# senseBox-CAM-M8Q_v21.net
KiCad netlist of a schematic drawn in EAGLE
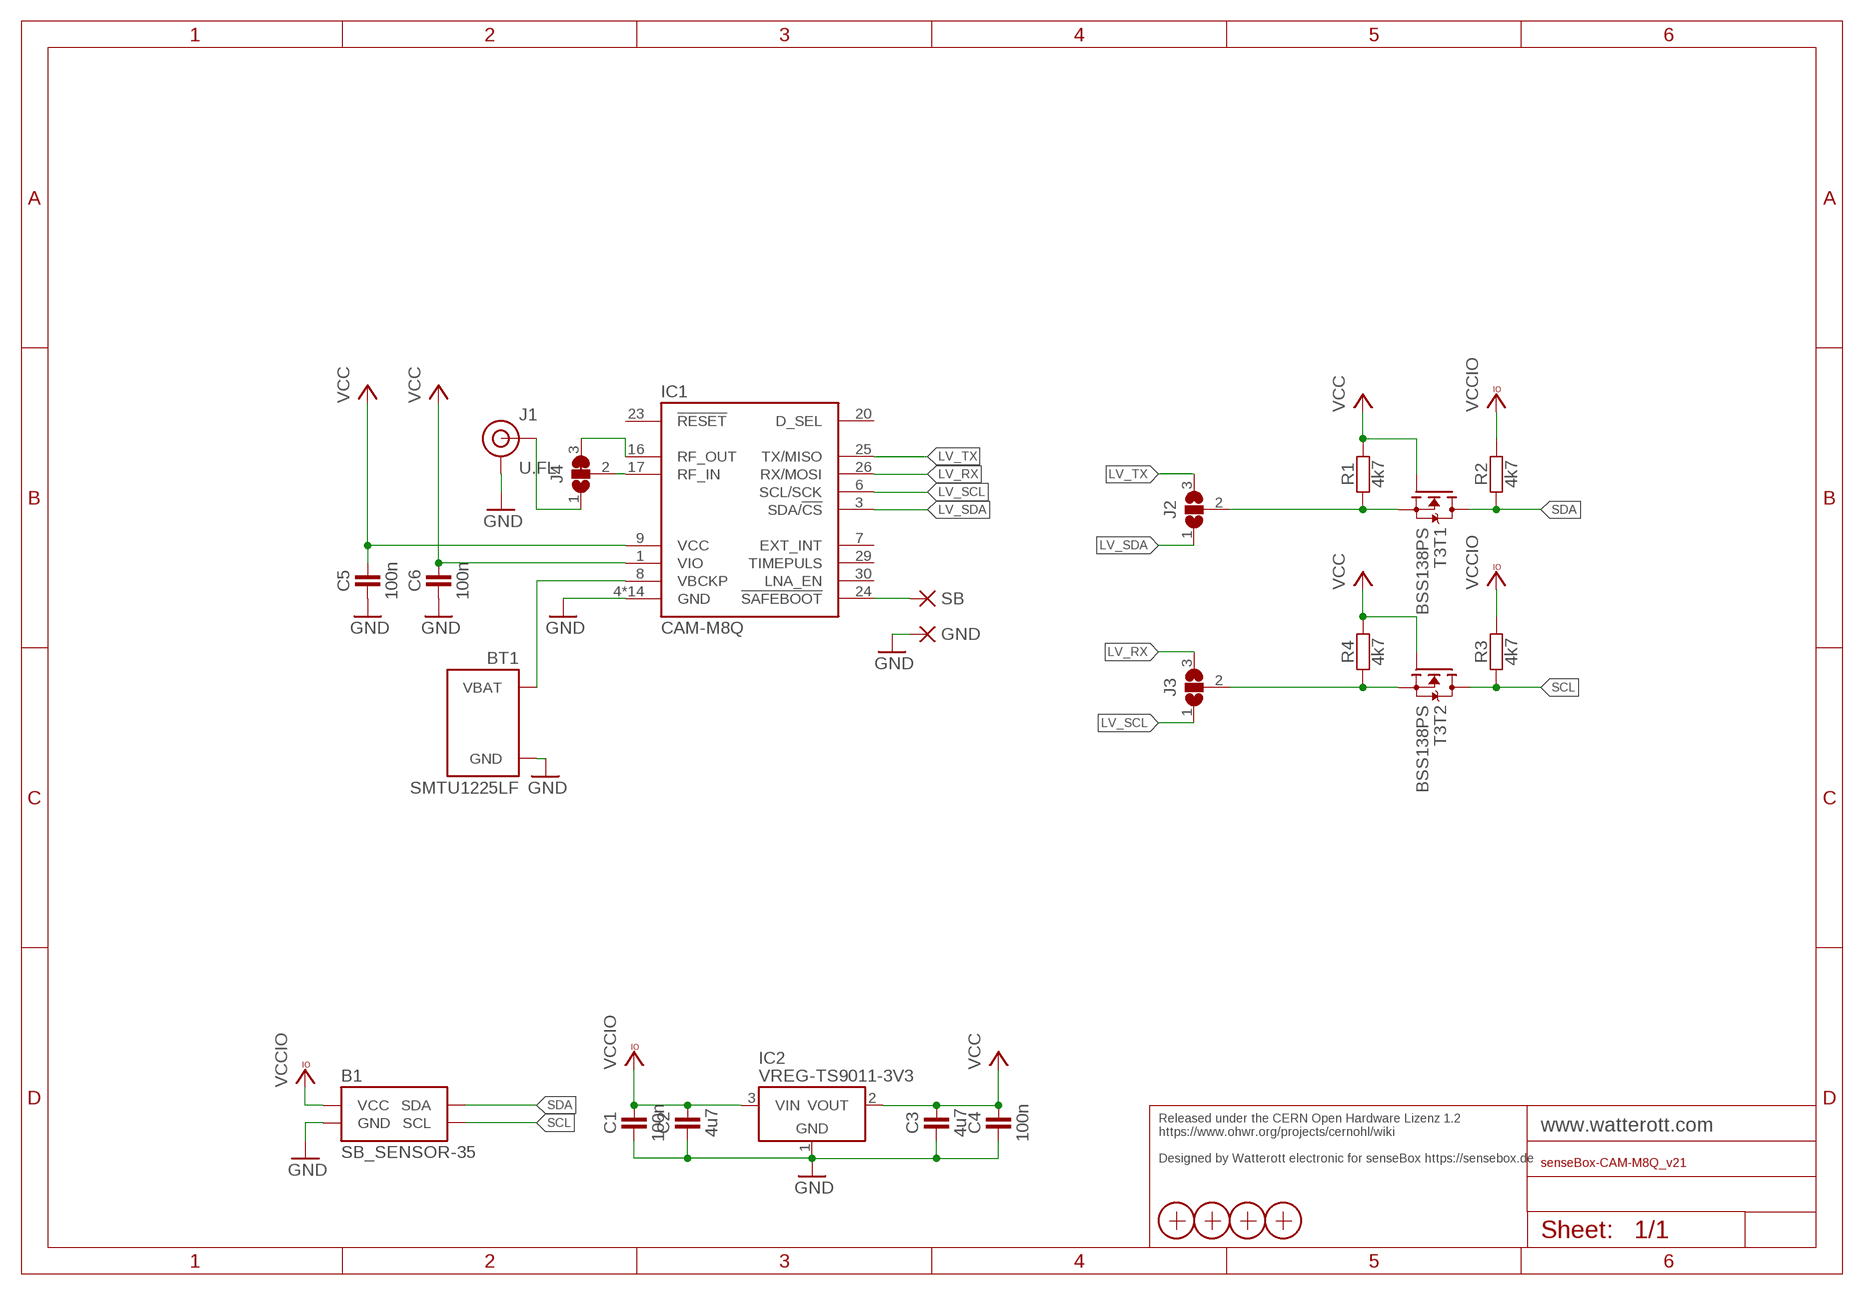
[diagram p0: schematic, sheet 1]

(export (version "E")
  (design (tool "Eeschema 10.0.6"))
  (components
    (comp (ref "B1")
      (value "SB_SENSOR-35")
      (footprint "eagle-import:SB-35X25")
      (libsource (lib "eagle-import") (part "SB_SENSOR-35"))
    )
    (comp (ref "BT1")
      (value "SMTU1225LF")
      (footprint "eagle-import:BAT-SMTU1225LF")
      (libsource (lib "eagle-import") (part "BATTERY-SMTU1225LF"))
    )
    (comp (ref "C1")
      (value "100n")
      (footprint "eagle-import:C0402")
      (libsource (lib "eagle-import") (part "CAPACITOR-0402"))
    )
    (comp (ref "C2")
      (value "4u7")
      (footprint "eagle-import:C0402")
      (libsource (lib "eagle-import") (part "CAPACITOR-0402"))
    )
    (comp (ref "C3")
      (value "4u7")
      (footprint "eagle-import:C0402")
      (libsource (lib "eagle-import") (part "CAPACITOR-0402"))
    )
    (comp (ref "C4")
      (value "100n")
      (footprint "eagle-import:C0402")
      (libsource (lib "eagle-import") (part "CAPACITOR-0402"))
    )
    (comp (ref "C5")
      (value "100n")
      (footprint "eagle-import:C0402")
      (libsource (lib "eagle-import") (part "CAPACITOR-0402"))
    )
    (comp (ref "C6")
      (value "100n")
      (footprint "eagle-import:C0402")
      (libsource (lib "eagle-import") (part "CAPACITOR-0402"))
    )
    (comp (ref "GND")
      (value "PAD-1.27X1.27_NC")
      (footprint "eagle-import:PAD-1.27X1.27_NC")
      (libsource (lib "eagle-import") (part "PAD-1.27X1.27_NC"))
    )
    (comp (ref "IC1")
      (value "CAM-M8Q")
      (footprint "eagle-import:CAM-M8Q")
      (libsource (lib "eagle-import") (part "CAM-M8Q"))
    )
    (comp (ref "IC2")
      (value "VREG-TS9011-3V3")
      (footprint "eagle-import:SOT23")
      (libsource (lib "eagle-import") (part "VREG-TS9011-3V3"))
    )
    (comp (ref "J1")
      (value "U.FL")
      (footprint "eagle-import:U.FL")
      (libsource (lib "eagle-import") (part "U.FL"))
    )
    (comp (ref "J2")
      (value "JUMPER3-0603-NC")
      (footprint "eagle-import:JUMPER3-0603_NC")
      (libsource (lib "eagle-import") (part "JUMPER3-0603-NC"))
    )
    (comp (ref "J3")
      (value "JUMPER3-0603-NC")
      (footprint "eagle-import:JUMPER3-0603_NC")
      (libsource (lib "eagle-import") (part "JUMPER3-0603-NC"))
    )
    (comp (ref "J4")
      (value "JUMPER3-0603")
      (footprint "eagle-import:JUMPER3-0603")
      (libsource (lib "eagle-import") (part "JUMPER3-0603"))
    )
    (comp (ref "R1")
      (value "4k7")
      (footprint "eagle-import:C0402")
      (libsource (lib "eagle-import") (part "RESISTOR-0402"))
    )
    (comp (ref "R2")
      (value "4k7")
      (footprint "eagle-import:C0402")
      (libsource (lib "eagle-import") (part "RESISTOR-0402"))
    )
    (comp (ref "R3")
      (value "4k7")
      (footprint "eagle-import:C0402")
      (libsource (lib "eagle-import") (part "RESISTOR-0402"))
    )
    (comp (ref "R4")
      (value "4k7")
      (footprint "eagle-import:C0402")
      (libsource (lib "eagle-import") (part "RESISTOR-0402"))
    )
    (comp (ref "SB")
      (value "PAD-1.27X1.27_NC")
      (footprint "eagle-import:PAD-1.27X1.27_NC")
      (libsource (lib "eagle-import") (part "PAD-1.27X1.27_NC"))
    )
    (comp (ref "T3")
      (value "BSS138PS")
      (footprint "eagle-import:SOT363")
      (libsource (lib "eagle-import") (part "BSS138PS"))
    )
    (comp (ref "X1")
      (value "PASSER-07")
      (footprint "eagle-import:PASSER_07MM")
      (libsource (lib "eagle-import") (part "PASSER-07"))
    )
    (comp (ref "X2")
      (value "PASSER-07")
      (footprint "eagle-import:PASSER_07MM")
      (libsource (lib "eagle-import") (part "PASSER-07"))
    )
    (comp (ref "X3")
      (value "PASSER-07")
      (footprint "eagle-import:PASSER_07MM")
      (libsource (lib "eagle-import") (part "PASSER-07"))
    )
    (comp (ref "X4")
      (value "PASSER-07")
      (footprint "eagle-import:PASSER_07MM")
      (libsource (lib "eagle-import") (part "PASSER-07"))
    )
  )
  (nets
    (net (code "1") (name "GND") (class "Default")
      (node (ref "B1") (pin "GND") (pinfunction "GND_GND") (pintype "power_in"))
      (node (ref "BT1") (pin "-") (pinfunction "GND_-") (pintype "power_in"))
      (node (ref "C1") (pin "1") (pinfunction "1_1") (pintype "passive"))
      (node (ref "C2") (pin "1") (pinfunction "1_1") (pintype "passive"))
      (node (ref "C3") (pin "1") (pinfunction "1_1") (pintype "passive"))
      (node (ref "C4") (pin "1") (pinfunction "1_1") (pintype "passive"))
      (node (ref "C5") (pin "1") (pinfunction "1_1") (pintype "passive"))
      (node (ref "C6") (pin "1") (pinfunction "1_1") (pintype "passive"))
      (node (ref "GND") (pin "1") (pinfunction "P_1") (pintype "passive"))
      (node (ref "IC1") (pin "10") (pinfunction "GND_10") (pintype "power_in"))
      (node (ref "IC1") (pin "11") (pinfunction "GND_11") (pintype "power_in"))
      (node (ref "IC1") (pin "12") (pinfunction "GND_12") (pintype "power_in"))
      (node (ref "IC1") (pin "13") (pinfunction "GND_13") (pintype "power_in"))
      (node (ref "IC1") (pin "14") (pinfunction "GND_14") (pintype "power_in"))
      (node (ref "IC1") (pin "15") (pinfunction "GND_15") (pintype "power_in"))
      (node (ref "IC1") (pin "18") (pinfunction "GND_18") (pintype "power_in"))
      (node (ref "IC1") (pin "19") (pinfunction "GND_19") (pintype "power_in"))
      (node (ref "IC1") (pin "21") (pinfunction "GND_21") (pintype "power_in"))
      (node (ref "IC1") (pin "22") (pinfunction "GND_22") (pintype "power_in"))
      (node (ref "IC1") (pin "27") (pinfunction "GND_27") (pintype "power_in"))
      (node (ref "IC1") (pin "31") (pinfunction "GND_31") (pintype "power_in"))
      (node (ref "IC1") (pin "4") (pinfunction "GND_4") (pintype "power_in"))
      (node (ref "IC1") (pin "5") (pinfunction "GND_5") (pintype "power_in"))
      (node (ref "IC2") (pin "1") (pinfunction "GND_1") (pintype "power_in"))
      (node (ref "J1") (pin "1") (pinfunction "GND_1") (pintype "bidirectional"))
      (node (ref "J1") (pin "2") (pinfunction "GND_2") (pintype "bidirectional"))
    )
    (net (code "2") (name "LV_RX") (class "Default")
      (node (ref "IC1") (pin "26") (pinfunction "RX/MOSI_26") (pintype "input"))
      (node (ref "J3") (pin "3") (pinfunction "3_3") (pintype "passive"))
    )
    (net (code "3") (name "LV_SCL") (class "Default")
      (node (ref "IC1") (pin "6") (pinfunction "SCL/SCK_6") (pintype "bidirectional"))
      (node (ref "J3") (pin "1") (pinfunction "1_1") (pintype "passive"))
    )
    (net (code "4") (name "LV_SDA") (class "Default")
      (node (ref "IC1") (pin "3") (pinfunction "SDA/~{CS}_3") (pintype "bidirectional"))
      (node (ref "J2") (pin "1") (pinfunction "1_1") (pintype "passive"))
    )
    (net (code "5") (name "LV_TX") (class "Default")
      (node (ref "IC1") (pin "25") (pinfunction "TX/MISO_25") (pintype "output"))
      (node (ref "J2") (pin "3") (pinfunction "3_3") (pintype "passive"))
    )
    (net (code "6") (name "Net-(BT1-VBAT)") (class "Default")
      (node (ref "BT1") (pin "+") (pinfunction "VBAT_+") (pintype "power_in"))
      (node (ref "IC1") (pin "8") (pinfunction "VBCKP_8") (pintype "power_in"))
    )
    (net (code "7") (name "Net-(IC1-RF_IN)") (class "Default")
      (node (ref "IC1") (pin "17") (pinfunction "RF_IN_17") (pintype "input"))
      (node (ref "J4") (pin "2") (pinfunction "2_2") (pintype "passive"))
    )
    (net (code "8") (name "Net-(IC1-RF_OUT)") (class "Default")
      (node (ref "IC1") (pin "16") (pinfunction "RF_OUT_16") (pintype "output"))
      (node (ref "J4") (pin "3") (pinfunction "3_3") (pintype "passive"))
    )
    (net (code "9") (name "Net-(IC1-~{SAFEBOOT})") (class "Default")
      (node (ref "IC1") (pin "24") (pinfunction "~{SAFEBOOT}_24") (pintype "bidirectional"))
      (node (ref "SB") (pin "1") (pinfunction "P_1") (pintype "passive"))
    )
    (net (code "10") (name "Net-(J1-SIGNAL)") (class "Default")
      (node (ref "J1") (pin "FEED") (pinfunction "SIGNAL_FEED") (pintype "bidirectional"))
      (node (ref "J4") (pin "1") (pinfunction "1_1") (pintype "passive"))
    )
    (net (code "11") (name "Net-(T3A-S)") (class "Default")
      (node (ref "J2") (pin "2") (pinfunction "2_2") (pintype "passive"))
      (node (ref "R1") (pin "1") (pinfunction "1_1") (pintype "passive"))
      (node (ref "T3") (pin "1") (pinfunction "S_1") (pintype "passive"))
    )
    (net (code "12") (name "Net-(T3B-S)") (class "Default")
      (node (ref "J3") (pin "2") (pinfunction "2_2") (pintype "passive"))
      (node (ref "R4") (pin "1") (pinfunction "1_1") (pintype "passive"))
      (node (ref "T3") (pin "4") (pinfunction "S_4") (pintype "passive"))
    )
    (net (code "13") (name "SCL") (class "Default")
      (node (ref "B1") (pin "SCL") (pinfunction "SCL_SCL") (pintype "bidirectional"))
      (node (ref "R3") (pin "1") (pinfunction "1_1") (pintype "passive"))
      (node (ref "T3") (pin "3") (pinfunction "D_3") (pintype "passive"))
    )
    (net (code "14") (name "SDA") (class "Default")
      (node (ref "B1") (pin "SDA") (pinfunction "SDA_SDA") (pintype "bidirectional"))
      (node (ref "R2") (pin "1") (pinfunction "1_1") (pintype "passive"))
      (node (ref "T3") (pin "6") (pinfunction "D_6") (pintype "passive"))
    )
    (net (code "15") (name "VCC") (class "Default")
      (node (ref "C3") (pin "2") (pinfunction "2_2") (pintype "passive"))
      (node (ref "C4") (pin "2") (pinfunction "2_2") (pintype "passive"))
      (node (ref "C5") (pin "2") (pinfunction "2_2") (pintype "passive"))
      (node (ref "C6") (pin "2") (pinfunction "2_2") (pintype "passive"))
      (node (ref "IC1") (pin "1") (pinfunction "VIO_1") (pintype "power_in"))
      (node (ref "IC1") (pin "9") (pinfunction "VCC_9") (pintype "power_in"))
      (node (ref "IC2") (pin "2") (pinfunction "VOUT_2") (pintype "power_in"))
      (node (ref "R1") (pin "2") (pinfunction "2_2") (pintype "passive"))
      (node (ref "R4") (pin "2") (pinfunction "2_2") (pintype "passive"))
      (node (ref "T3") (pin "2") (pinfunction "G_2") (pintype "passive"))
      (node (ref "T3") (pin "5") (pinfunction "G_5") (pintype "passive"))
    )
    (net (code "16") (name "VCCIO") (class "Default")
      (node (ref "B1") (pin "VCC") (pinfunction "VCC_VCC") (pintype "power_in"))
      (node (ref "C1") (pin "2") (pinfunction "2_2") (pintype "passive"))
      (node (ref "C2") (pin "2") (pinfunction "2_2") (pintype "passive"))
      (node (ref "IC2") (pin "3") (pinfunction "VIN_3") (pintype "power_in"))
      (node (ref "R2") (pin "2") (pinfunction "2_2") (pintype "passive"))
      (node (ref "R3") (pin "2") (pinfunction "2_2") (pintype "passive"))
    )
    (net (code "17") (name "unconnected-(IC1-D_SEL-Pad20)") (class "Default")
      (node (ref "IC1") (pin "20") (pinfunction "D_SEL_20") (pintype "bidirectional"))
    )
    (net (code "18") (name "unconnected-(IC1-EXT_INT-Pad7)") (class "Default")
      (node (ref "IC1") (pin "7") (pinfunction "EXT_INT_7") (pintype "bidirectional"))
    )
    (net (code "19") (name "unconnected-(IC1-LNA_EN-Pad30)") (class "Default")
      (node (ref "IC1") (pin "30") (pinfunction "LNA_EN_30") (pintype "bidirectional"))
    )
    (net (code "20") (name "unconnected-(IC1-TIMEPULS-Pad29)") (class "Default")
      (node (ref "IC1") (pin "29") (pinfunction "TIMEPULS_29") (pintype "output"))
    )
    (net (code "21") (name "unconnected-(IC1-~{RESET}-Pad23)") (class "Default")
      (node (ref "IC1") (pin "23") (pinfunction "~{RESET}_23") (pintype "input"))
    )
  )
)
